# WorkingVersion_Final_Bread_Proofing_Box_.net
KiCad netlist of a schematic drawn in EAGLE
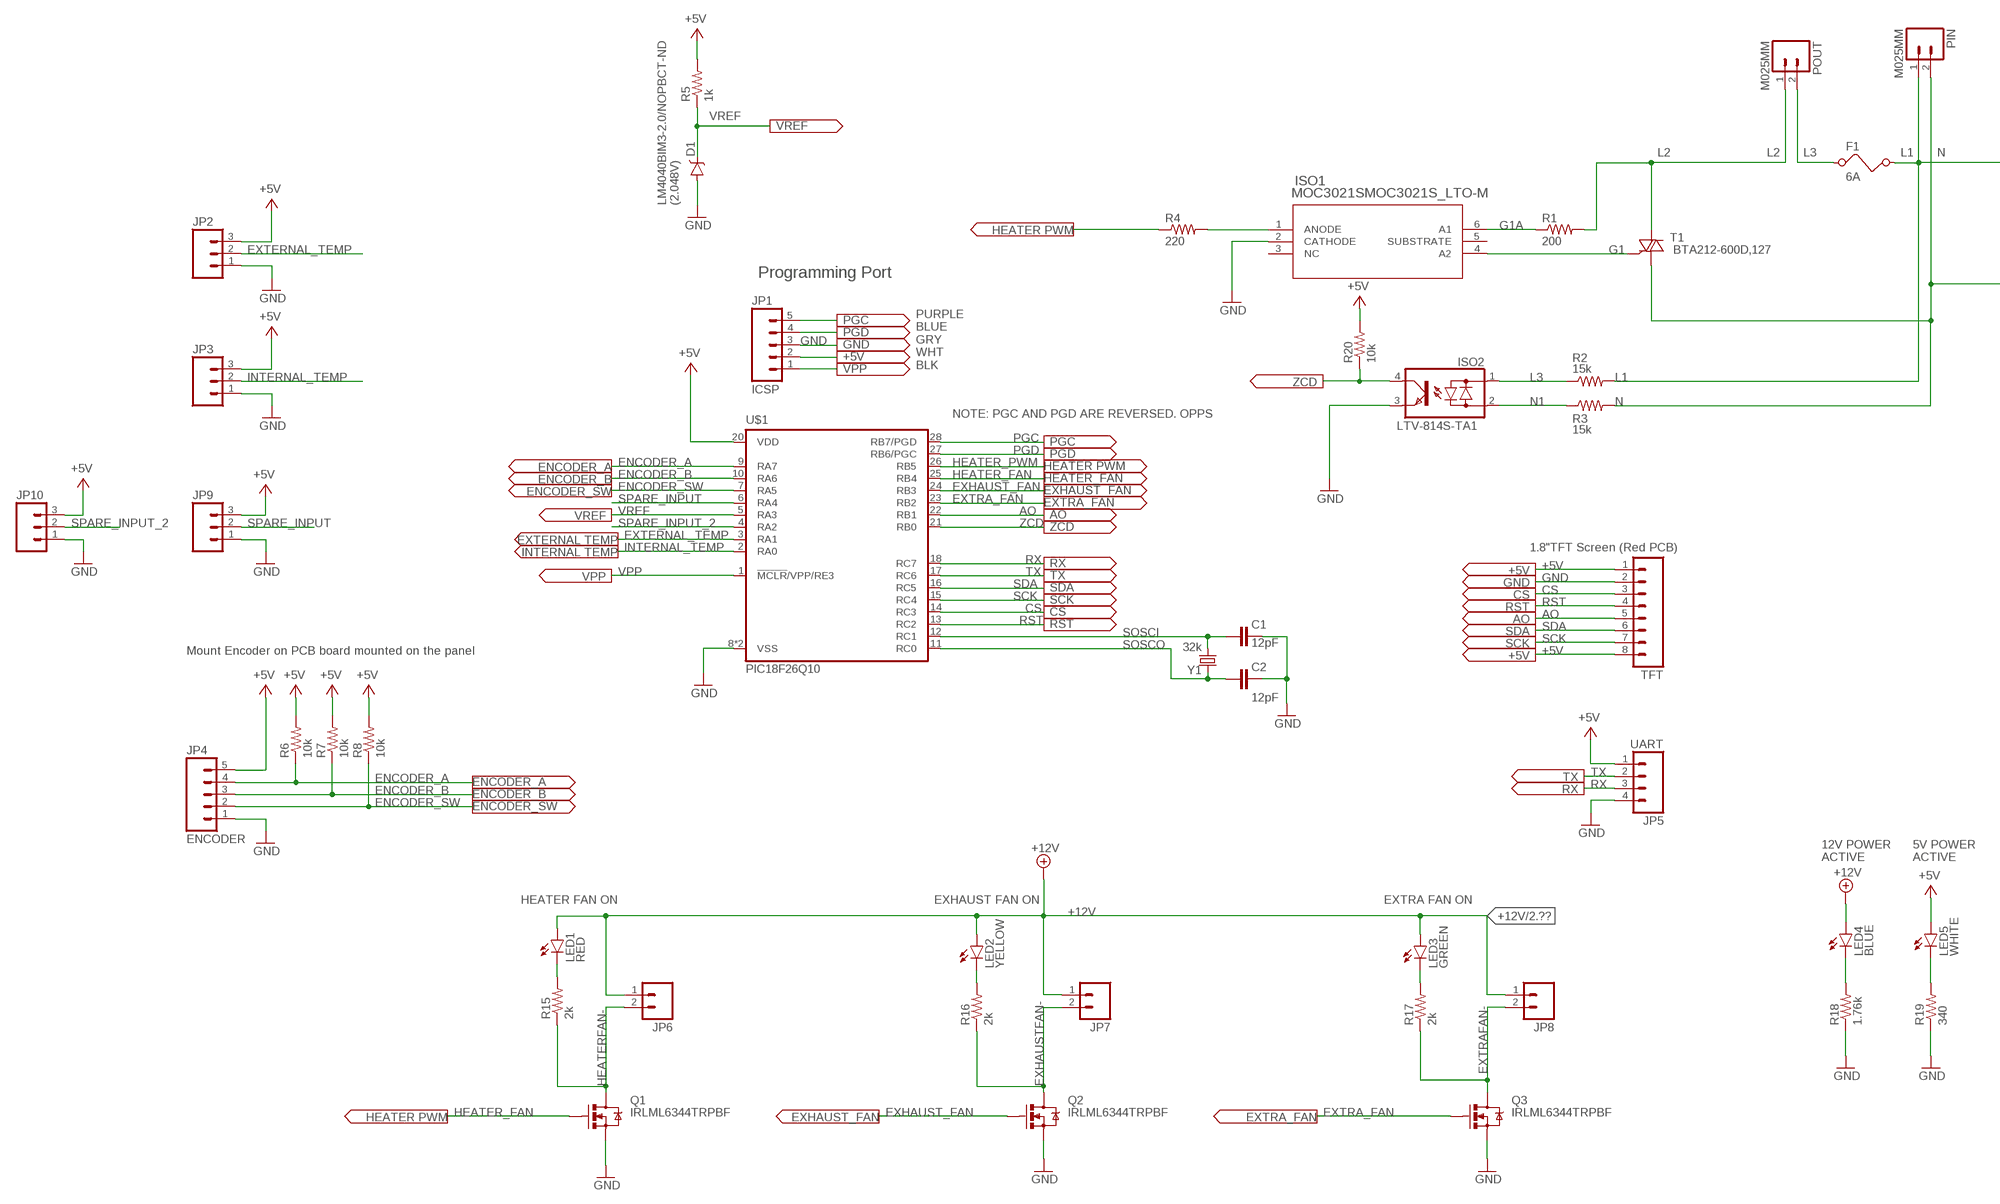
[diagram p0: schematic, sheet 1, part 1 of 2]
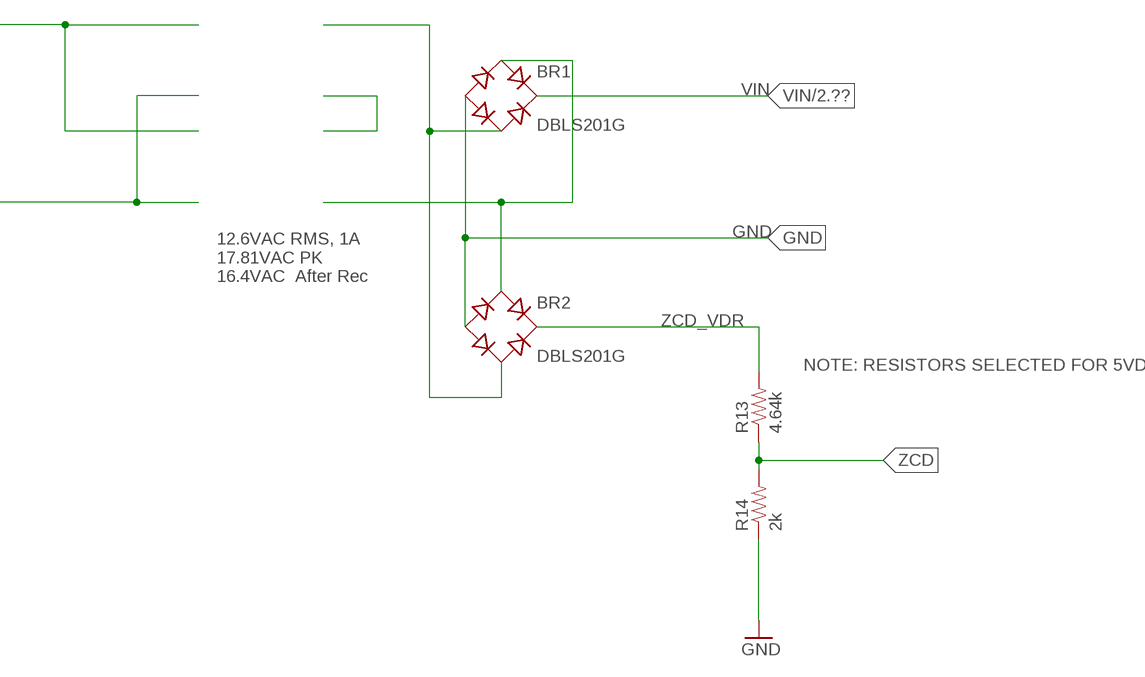
[diagram p1: schematic, sheet 1, part 2 of 2]
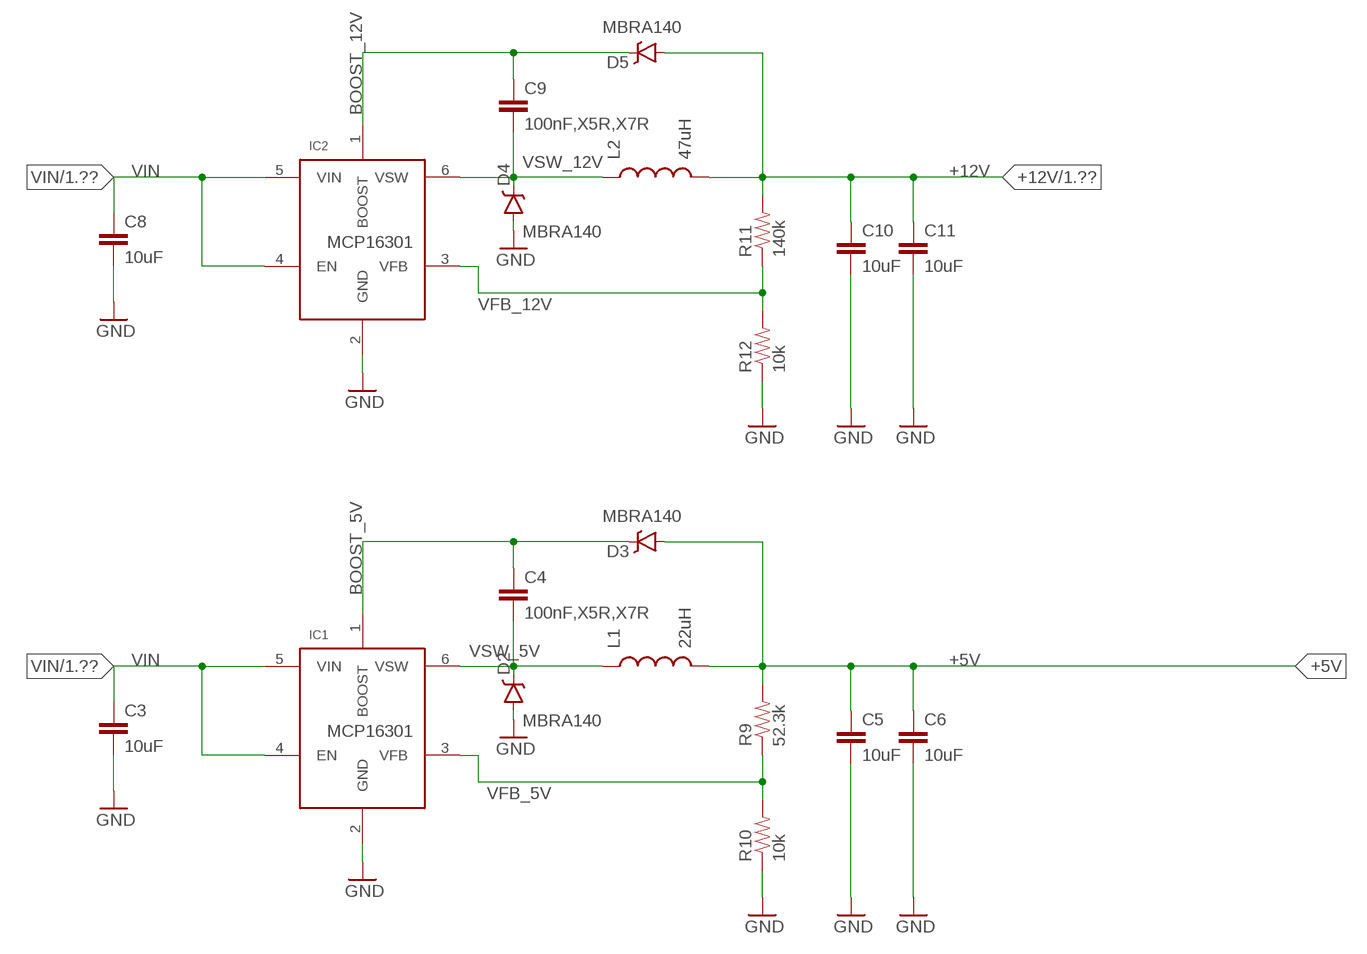
[diagram p2: schematic, sheet 2]

(export (version "E")
  (design (tool "Eeschema 10.0.6"))
  (components
    (comp (ref "C3")
      (value "10uF")
      (footprint "eagle-import:1206")
      (libsource (lib "eagle-import") (part "CAP1206"))
    )
    (comp (ref "C4")
      (value "100nF,X5R,X7R")
      (footprint "eagle-import:1206")
      (libsource (lib "eagle-import") (part "CAP1206"))
    )
    (comp (ref "C5")
      (value "10uF")
      (footprint "eagle-import:1206")
      (libsource (lib "eagle-import") (part "CAP1206"))
    )
    (comp (ref "C6")
      (value "10uF")
      (footprint "eagle-import:1206")
      (libsource (lib "eagle-import") (part "CAP1206"))
    )
    (comp (ref "C8")
      (value "10uF")
      (footprint "eagle-import:1206")
      (libsource (lib "eagle-import") (part "CAP1206"))
    )
    (comp (ref "C9")
      (value "100nF,X5R,X7R")
      (footprint "eagle-import:1206")
      (libsource (lib "eagle-import") (part "CAP1206"))
    )
    (comp (ref "C10")
      (value "10uF")
      (footprint "eagle-import:1206")
      (libsource (lib "eagle-import") (part "CAP1206"))
    )
    (comp (ref "C11")
      (value "10uF")
      (footprint "eagle-import:1206")
      (libsource (lib "eagle-import") (part "CAP1206"))
    )
    (comp (ref "D2")
      (value "MBRA140")
      (footprint "eagle-import:SMA-DIODE")
      (libsource (lib "eagle-import") (part "DIODE-SCHOTTKY-MBRA140"))
    )
    (comp (ref "D3")
      (value "MBRA140")
      (footprint "eagle-import:SMA-DIODE")
      (libsource (lib "eagle-import") (part "DIODE-SCHOTTKY-MBRA140"))
    )
    (comp (ref "D4")
      (value "MBRA140")
      (footprint "eagle-import:SMA-DIODE")
      (libsource (lib "eagle-import") (part "DIODE-SCHOTTKY-MBRA140"))
    )
    (comp (ref "D5")
      (value "MBRA140")
      (footprint "eagle-import:SMA-DIODE")
      (libsource (lib "eagle-import") (part "DIODE-SCHOTTKY-MBRA140"))
    )
    (comp (ref "IC1")
      (value "MCP16301")
      (footprint "eagle-import:SOT23-6")
      (libsource (lib "eagle-import") (part "MCP16301"))
    )
    (comp (ref "IC2")
      (value "MCP16301")
      (footprint "eagle-import:SOT23-6")
      (libsource (lib "eagle-import") (part "MCP16301"))
    )
    (comp (ref "L1")
      (value "22uH")
      (footprint "eagle-import:1210")
      (libsource (lib "eagle-import") (part "INDUCTOR1210"))
    )
    (comp (ref "L2")
      (value "47uH")
      (footprint "eagle-import:1210")
      (libsource (lib "eagle-import") (part "INDUCTOR1210"))
    )
    (comp (ref "R9")
      (value "52.3k")
      (footprint "eagle-import:1206")
      (libsource (lib "eagle-import") (part "RESISTOR1206"))
    )
    (comp (ref "R10")
      (value "10k")
      (footprint "eagle-import:1206")
      (libsource (lib "eagle-import") (part "RESISTOR1206"))
    )
    (comp (ref "R11")
      (value "140k")
      (footprint "eagle-import:1206")
      (libsource (lib "eagle-import") (part "RESISTOR1206"))
    )
    (comp (ref "R12")
      (value "10k")
      (footprint "eagle-import:1206")
      (libsource (lib "eagle-import") (part "RESISTOR1206"))
    )
    (comp (ref "BR1")
      (value "DBLS201G")
      (footprint "eagle-import:DBS")
      (libsource (lib "eagle-import") (part "DB?GLS201"))
    )
    (comp (ref "BR2")
      (value "DBLS201G")
      (footprint "eagle-import:DBS")
      (libsource (lib "eagle-import") (part "DB?GLS201"))
    )
    (comp (ref "C1")
      (value "12pF")
      (footprint "eagle-import:0805")
      (libsource (lib "eagle-import") (part "CAP0805"))
    )
    (comp (ref "C2")
      (value "12pF")
      (footprint "eagle-import:0805")
      (libsource (lib "eagle-import") (part "CAP0805"))
    )
    (comp (ref "D1")
      (value "V-REFERENCESMD")
      (footprint "eagle-import:SOT23-3")
      (libsource (lib "eagle-import") (part "V-REFERENCESMD"))
    )
    (comp (ref "F1")
      (value "6A")
      (footprint "eagle-import:FUSE")
      (libsource (lib "eagle-import") (part "FUSE"))
    )
    (comp (ref "ISO1")
      (value "MOC3021SMOC3021S_LTO-M")
      (footprint "eagle-import:MOC3021S_LTO-M")
      (fields
        (field (name "MANUFACTURER_PART_NUMBER") "MOC3021S")
        (field (name "COPYRIGHT") "Copyright (C) 2018 Accelerated Designs. All rights reserved")
      )
      (libsource (lib "eagle-import") (part "MOC3021SMOC3021S_LTO-M"))
    )
    (comp (ref "ISO2")
      (value "LTV-814S-TA1")
      (footprint "eagle-import:DIL4-SMD")
      (fields (field (name "MF") "VISHAY/TELEFUNKEN") (field (name "MPN") "SFH6206-3"))
      (libsource (lib "eagle-import") (part "SFH6206"))
    )
    (comp (ref "JP1")
      (value "ICSP")
      (footprint "eagle-import:1X05")
      (libsource (lib "eagle-import") (part "M05PTH"))
    )
    (comp (ref "JP2")
      (value "M03POLAR")
      (footprint "eagle-import:MOLEX-1X3")
      (libsource (lib "eagle-import") (part "M03POLAR"))
    )
    (comp (ref "JP3")
      (value "M03POLAR")
      (footprint "eagle-import:MOLEX-1X3")
      (libsource (lib "eagle-import") (part "M03POLAR"))
    )
    (comp (ref "JP4")
      (value "ENCODER")
      (footprint "eagle-import:1X05")
      (libsource (lib "eagle-import") (part "M05PTH"))
    )
    (comp (ref "JP5")
      (value "UART")
      (footprint "eagle-import:1X04_LOCK")
      (libsource (lib "eagle-import") (part "M04LOCK"))
    )
    (comp (ref "JP6")
      (value "M02POLAR_LOCK")
      (footprint "eagle-import:MOLEX-1X2_LOCK")
      (libsource (lib "eagle-import") (part "M02POLAR_LOCK"))
    )
    (comp (ref "JP7")
      (value "M02POLAR_LOCK")
      (footprint "eagle-import:MOLEX-1X2_LOCK")
      (libsource (lib "eagle-import") (part "M02POLAR_LOCK"))
    )
    (comp (ref "JP8")
      (value "M02POLAR_LOCK")
      (footprint "eagle-import:MOLEX-1X2_LOCK")
      (libsource (lib "eagle-import") (part "M02POLAR_LOCK"))
    )
    (comp (ref "JP9")
      (value "M03POLAR")
      (footprint "eagle-import:MOLEX-1X3")
      (libsource (lib "eagle-import") (part "M03POLAR"))
    )
    (comp (ref "JP10")
      (value "M03POLAR")
      (footprint "eagle-import:MOLEX-1X3")
      (libsource (lib "eagle-import") (part "M03POLAR"))
    )
    (comp (ref "LED1")
      (value "RED")
      (footprint "eagle-import:LED-1206")
      (libsource (lib "eagle-import") (part "LED1206"))
    )
    (comp (ref "LED2")
      (value "YELLOW")
      (footprint "eagle-import:LED-1206")
      (libsource (lib "eagle-import") (part "LED1206"))
    )
    (comp (ref "LED3")
      (value "GREEN")
      (footprint "eagle-import:LED-1206")
      (libsource (lib "eagle-import") (part "LED1206"))
    )
    (comp (ref "LED4")
      (value "BLUE")
      (footprint "eagle-import:LED-1206")
      (libsource (lib "eagle-import") (part "LED1206"))
    )
    (comp (ref "LED5")
      (value "WHITE")
      (footprint "eagle-import:LED-1206")
      (libsource (lib "eagle-import") (part "LED1206"))
    )
    (comp (ref "PIN")
      (value "M025MM")
      (footprint "eagle-import:SCREWTERMINAL-5MM-2")
      (libsource (lib "eagle-import") (part "M025MM"))
    )
    (comp (ref "POUT")
      (value "M025MM")
      (footprint "eagle-import:SCREWTERMINAL-5MM-2")
      (libsource (lib "eagle-import") (part "M025MM"))
    )
    (comp (ref "Q1")
      (value "IRLML6344TRPBF")
      (footprint "eagle-import:SOT323")
      (libsource (lib "eagle-import") (part "MOSFET-NCHANNEL2N7002PW"))
    )
    (comp (ref "Q2")
      (value "IRLML6344TRPBF")
      (footprint "eagle-import:SOT323")
      (libsource (lib "eagle-import") (part "MOSFET-NCHANNEL2N7002PW"))
    )
    (comp (ref "Q3")
      (value "IRLML6344TRPBF")
      (footprint "eagle-import:SOT323")
      (libsource (lib "eagle-import") (part "MOSFET-NCHANNEL2N7002PW"))
    )
    (comp (ref "R1")
      (value "200")
      (footprint "eagle-import:R2512")
      (libsource (lib "eagle-import") (part "R-US_R2512"))
    )
    (comp (ref "R2")
      (value "15k")
      (footprint "eagle-import:R2512")
      (libsource (lib "eagle-import") (part "R-US_R2512"))
    )
    (comp (ref "R3")
      (value "15k")
      (footprint "eagle-import:R2512")
      (libsource (lib "eagle-import") (part "R-US_R2512"))
    )
    (comp (ref "R4")
      (value "220")
      (footprint "eagle-import:1206")
      (libsource (lib "eagle-import") (part "RESISTOR1206"))
    )
    (comp (ref "R5")
      (value "1k")
      (footprint "eagle-import:1206")
      (libsource (lib "eagle-import") (part "RESISTOR1206"))
    )
    (comp (ref "R6")
      (value "10k")
      (footprint "eagle-import:1206")
      (libsource (lib "eagle-import") (part "RESISTOR1206"))
    )
    (comp (ref "R7")
      (value "10k")
      (footprint "eagle-import:1206")
      (libsource (lib "eagle-import") (part "RESISTOR1206"))
    )
    (comp (ref "R8")
      (value "10k")
      (footprint "eagle-import:1206")
      (libsource (lib "eagle-import") (part "RESISTOR1206"))
    )
    (comp (ref "R13")
      (value "4.64k")
      (footprint "eagle-import:1206")
      (libsource (lib "eagle-import") (part "RESISTOR1206"))
    )
    (comp (ref "R14")
      (value "2k")
      (footprint "eagle-import:1206")
      (libsource (lib "eagle-import") (part "RESISTOR1206"))
    )
    (comp (ref "R15")
      (value "2k")
      (footprint "eagle-import:1206")
      (libsource (lib "eagle-import") (part "RESISTOR1206"))
    )
    (comp (ref "R16")
      (value "2k")
      (footprint "eagle-import:1206")
      (libsource (lib "eagle-import") (part "RESISTOR1206"))
    )
    (comp (ref "R17")
      (value "2k")
      (footprint "eagle-import:1206")
      (libsource (lib "eagle-import") (part "RESISTOR1206"))
    )
    (comp (ref "R18")
      (value "1.76k")
      (footprint "eagle-import:1206")
      (libsource (lib "eagle-import") (part "RESISTOR1206"))
    )
    (comp (ref "R19")
      (value "340")
      (footprint "eagle-import:1206")
      (libsource (lib "eagle-import") (part "RESISTOR1206"))
    )
    (comp (ref "R20")
      (value "10k")
      (footprint "eagle-import:1206")
      (libsource (lib "eagle-import") (part "RESISTOR1206"))
    )
    (comp (ref "T1")
      (value "BTA212-600D,127")
      (footprint "eagle-import:TO220BV")
      (libsource (lib "eagle-import") (part "BT138-V"))
    )
    (comp (ref "TFT")
      (value "M08LOCK")
      (footprint "eagle-import:1X08_LOCK")
      (libsource (lib "eagle-import") (part "M08LOCK"))
    )
    (comp (ref "U$1")
      (value "PIC18F26Q10")
      (footprint "eagle-import:SO28W")
      (libsource (lib "eagle-import") (part "PIC18F25K22SOIC"))
    )
    (comp (ref "Y1")
      (value "32k")
      (footprint "eagle-import:TC26V")
      (libsource (lib "eagle-import") (part "CRYSTALTC26V"))
    )
  )
  (nets
    (net (code "1") (name "+5V") (class "Default")
      (node (ref "C5") (pin "1") (pinfunction "1_1") (pintype "passive"))
      (node (ref "C6") (pin "1") (pinfunction "1_1") (pintype "passive"))
      (node (ref "D3") (pin "A") (pinfunction "A_A") (pintype "passive"))
      (node (ref "JP1") (pin "2") (pinfunction "2_2") (pintype "passive"))
      (node (ref "JP10") (pin "3") (pinfunction "3_3") (pintype "passive"))
      (node (ref "JP2") (pin "3") (pinfunction "3_3") (pintype "passive"))
      (node (ref "JP3") (pin "3") (pinfunction "3_3") (pintype "passive"))
      (node (ref "JP4") (pin "5") (pinfunction "5_5") (pintype "passive"))
      (node (ref "JP5") (pin "1") (pinfunction "1_1") (pintype "passive"))
      (node (ref "JP9") (pin "3") (pinfunction "3_3") (pintype "passive"))
      (node (ref "L1") (pin "2") (pinfunction "2_2") (pintype "passive"))
      (node (ref "LED5") (pin "A") (pinfunction "A_A") (pintype "passive"))
      (node (ref "R20") (pin "2") (pinfunction "2_2") (pintype "passive"))
      (node (ref "R5") (pin "2") (pinfunction "2_2") (pintype "passive"))
      (node (ref "R6") (pin "2") (pinfunction "2_2") (pintype "passive"))
      (node (ref "R7") (pin "2") (pinfunction "2_2") (pintype "passive"))
      (node (ref "R8") (pin "2") (pinfunction "2_2") (pintype "passive"))
      (node (ref "R9") (pin "2") (pinfunction "2_2") (pintype "passive"))
      (node (ref "TFT") (pin "1") (pinfunction "1_1") (pintype "passive"))
      (node (ref "TFT") (pin "8") (pinfunction "8_8") (pintype "passive"))
      (node (ref "U$1") (pin "20") (pinfunction "VDD_20") (pintype "power_in"))
    )
    (net (code "2") (name "+12V") (class "Default")
      (node (ref "C10") (pin "1") (pinfunction "1_1") (pintype "passive"))
      (node (ref "C11") (pin "1") (pinfunction "1_1") (pintype "passive"))
      (node (ref "D5") (pin "A") (pinfunction "A_A") (pintype "passive"))
      (node (ref "JP6") (pin "1") (pinfunction "1_1") (pintype "passive"))
      (node (ref "JP7") (pin "1") (pinfunction "1_1") (pintype "passive"))
      (node (ref "JP8") (pin "1") (pinfunction "1_1") (pintype "passive"))
      (node (ref "L2") (pin "2") (pinfunction "2_2") (pintype "passive"))
      (node (ref "LED1") (pin "A") (pinfunction "A_A") (pintype "passive"))
      (node (ref "LED2") (pin "A") (pinfunction "A_A") (pintype "passive"))
      (node (ref "LED3") (pin "A") (pinfunction "A_A") (pintype "passive"))
      (node (ref "LED4") (pin "A") (pinfunction "A_A") (pintype "passive"))
      (node (ref "R11") (pin "2") (pinfunction "2_2") (pintype "passive"))
    )
    (net (code "3") (name "AO") (class "Default")
      (node (ref "TFT") (pin "5") (pinfunction "5_5") (pintype "passive"))
      (node (ref "U$1") (pin "22") (pinfunction "RB1_22") (pintype "bidirectional"))
    )
    (net (code "4") (name "BOOST_5V") (class "Default")
      (node (ref "C4") (pin "1") (pinfunction "1_1") (pintype "passive"))
      (node (ref "D3") (pin "C") (pinfunction "C_C") (pintype "passive"))
      (node (ref "IC1") (pin "1") (pinfunction "BOOST_1") (pintype "bidirectional"))
    )
    (net (code "5") (name "BOOST_12V") (class "Default")
      (node (ref "C9") (pin "1") (pinfunction "1_1") (pintype "passive"))
      (node (ref "D5") (pin "C") (pinfunction "C_C") (pintype "passive"))
      (node (ref "IC2") (pin "1") (pinfunction "BOOST_1") (pintype "bidirectional"))
    )
    (net (code "6") (name "CS") (class "Default")
      (node (ref "TFT") (pin "3") (pinfunction "3_3") (pintype "passive"))
      (node (ref "U$1") (pin "14") (pinfunction "RC3_14") (pintype "bidirectional"))
    )
    (net (code "7") (name "ENCODER_A") (class "Default")
      (node (ref "JP4") (pin "4") (pinfunction "4_4") (pintype "passive"))
      (node (ref "R6") (pin "1") (pinfunction "1_1") (pintype "passive"))
      (node (ref "U$1") (pin "9") (pinfunction "RA7_9") (pintype "bidirectional"))
    )
    (net (code "8") (name "ENCODER_B") (class "Default")
      (node (ref "JP4") (pin "3") (pinfunction "3_3") (pintype "passive"))
      (node (ref "R7") (pin "1") (pinfunction "1_1") (pintype "passive"))
      (node (ref "U$1") (pin "10") (pinfunction "RA6_10") (pintype "bidirectional"))
    )
    (net (code "9") (name "ENCODER_SW") (class "Default")
      (node (ref "JP4") (pin "2") (pinfunction "2_2") (pintype "passive"))
      (node (ref "R8") (pin "1") (pinfunction "1_1") (pintype "passive"))
      (node (ref "U$1") (pin "7") (pinfunction "RA5_7") (pintype "bidirectional"))
    )
    (net (code "10") (name "EXHAUSTFAN-") (class "Default")
      (node (ref "JP7") (pin "2") (pinfunction "2_2") (pintype "passive"))
      (node (ref "Q2") (pin "3") (pinfunction "D_3") (pintype "passive"))
      (node (ref "R16") (pin "1") (pinfunction "1_1") (pintype "passive"))
    )
    (net (code "11") (name "EXHAUST_FAN") (class "Default")
      (node (ref "Q2") (pin "1") (pinfunction "G_1") (pintype "passive"))
      (node (ref "U$1") (pin "24") (pinfunction "RB3_24") (pintype "bidirectional"))
    )
    (net (code "12") (name "EXTERNAL_TEMP") (class "Default")
      (node (ref "JP2") (pin "2") (pinfunction "2_2") (pintype "passive"))
      (node (ref "U$1") (pin "3") (pinfunction "RA1_3") (pintype "bidirectional"))
    )
    (net (code "13") (name "EXTRAFAN-") (class "Default")
      (node (ref "JP8") (pin "2") (pinfunction "2_2") (pintype "passive"))
      (node (ref "Q3") (pin "3") (pinfunction "D_3") (pintype "passive"))
      (node (ref "R17") (pin "1") (pinfunction "1_1") (pintype "passive"))
    )
    (net (code "14") (name "EXTRA_FAN") (class "Default")
      (node (ref "Q3") (pin "1") (pinfunction "G_1") (pintype "passive"))
      (node (ref "U$1") (pin "23") (pinfunction "RB2_23") (pintype "bidirectional"))
    )
    (net (code "15") (name "G1") (class "Default")
      (node (ref "ISO1") (pin "4") (pinfunction "A2_4") (pintype "passive"))
      (node (ref "T1") (pin "G") (pinfunction "G_G") (pintype "passive"))
    )
    (net (code "16") (name "G1A") (class "Default")
      (node (ref "ISO1") (pin "6") (pinfunction "A1_6") (pintype "passive"))
      (node (ref "R1") (pin "1") (pinfunction "1_1") (pintype "passive"))
    )
    (net (code "17") (name "GND") (class "Default")
      (node (ref "BR1") (pin "-") (pinfunction "-_-") (pintype "passive"))
      (node (ref "BR2") (pin "-") (pinfunction "-_-") (pintype "passive"))
      (node (ref "C1") (pin "2") (pinfunction "2_2") (pintype "passive"))
      (node (ref "C10") (pin "2") (pinfunction "2_2") (pintype "passive"))
      (node (ref "C11") (pin "2") (pinfunction "2_2") (pintype "passive"))
      (node (ref "C2") (pin "2") (pinfunction "2_2") (pintype "passive"))
      (node (ref "C3") (pin "2") (pinfunction "2_2") (pintype "passive"))
      (node (ref "C5") (pin "2") (pinfunction "2_2") (pintype "passive"))
      (node (ref "C6") (pin "2") (pinfunction "2_2") (pintype "passive"))
      (node (ref "C8") (pin "2") (pinfunction "2_2") (pintype "passive"))
      (node (ref "D1") (pin "2") (pinfunction "A_2") (pintype "passive"))
      (node (ref "D2") (pin "A") (pinfunction "A_A") (pintype "passive"))
      (node (ref "D4") (pin "A") (pinfunction "A_A") (pintype "passive"))
      (node (ref "IC1") (pin "2") (pinfunction "GND_2") (pintype "bidirectional"))
      (node (ref "IC2") (pin "2") (pinfunction "GND_2") (pintype "bidirectional"))
      (node (ref "ISO1") (pin "2") (pinfunction "CATHODE_2") (pintype "passive"))
      (node (ref "ISO2") (pin "3") (pinfunction "E_3") (pintype "passive"))
      (node (ref "JP1") (pin "3") (pinfunction "3_3") (pintype "passive"))
      (node (ref "JP10") (pin "1") (pinfunction "1_1") (pintype "passive"))
      (node (ref "JP2") (pin "1") (pinfunction "1_1") (pintype "passive"))
      (node (ref "JP3") (pin "1") (pinfunction "1_1") (pintype "passive"))
      (node (ref "JP4") (pin "1") (pinfunction "1_1") (pintype "passive"))
      (node (ref "JP5") (pin "4") (pinfunction "4_4") (pintype "passive"))
      (node (ref "JP9") (pin "1") (pinfunction "1_1") (pintype "passive"))
      (node (ref "Q1") (pin "2") (pinfunction "S_2") (pintype "passive"))
      (node (ref "Q2") (pin "2") (pinfunction "S_2") (pintype "passive"))
      (node (ref "Q3") (pin "2") (pinfunction "S_2") (pintype "passive"))
      (node (ref "R10") (pin "1") (pinfunction "1_1") (pintype "passive"))
      (node (ref "R12") (pin "1") (pinfunction "1_1") (pintype "passive"))
      (node (ref "R14") (pin "1") (pinfunction "1_1") (pintype "passive"))
      (node (ref "R18") (pin "1") (pinfunction "1_1") (pintype "passive"))
      (node (ref "R19") (pin "1") (pinfunction "1_1") (pintype "passive"))
      (node (ref "TFT") (pin "2") (pinfunction "2_2") (pintype "passive"))
      (node (ref "U$1") (pin "19") (pinfunction "VSS_19") (pintype "power_in"))
      (node (ref "U$1") (pin "8") (pinfunction "VSS_8") (pintype "power_in"))
    )
    (net (code "18") (name "HEATERFAN-") (class "Default")
      (node (ref "JP6") (pin "2") (pinfunction "2_2") (pintype "passive"))
      (node (ref "Q1") (pin "3") (pinfunction "D_3") (pintype "passive"))
      (node (ref "R15") (pin "1") (pinfunction "1_1") (pintype "passive"))
    )
    (net (code "19") (name "HEATER_FAN") (class "Default")
      (node (ref "Q1") (pin "1") (pinfunction "G_1") (pintype "passive"))
      (node (ref "U$1") (pin "25") (pinfunction "RB4_25") (pintype "bidirectional"))
    )
    (net (code "20") (name "HEATER_PWM") (class "Default")
      (node (ref "R4") (pin "1") (pinfunction "1_1") (pintype "passive"))
      (node (ref "U$1") (pin "26") (pinfunction "RB5_26") (pintype "bidirectional"))
    )
    (net (code "21") (name "INTERNAL_TEMP") (class "Default")
      (node (ref "JP3") (pin "2") (pinfunction "2_2") (pintype "passive"))
      (node (ref "U$1") (pin "2") (pinfunction "RA0_2") (pintype "bidirectional"))
    )
    (net (code "22") (name "L1") (class "Default")
      (node (ref "F1") (pin "2") (pinfunction "2_2") (pintype "passive"))
      (node (ref "PIN") (pin "1") (pinfunction "1_1") (pintype "passive"))
      (node (ref "R2") (pin "2") (pinfunction "2_2") (pintype "passive"))
    )
    (net (code "23") (name "L2") (class "Default")
      (node (ref "POUT") (pin "1") (pinfunction "1_1") (pintype "passive"))
      (node (ref "R1") (pin "2") (pinfunction "2_2") (pintype "passive"))
      (node (ref "T1") (pin "T2") (pinfunction "A2_T2") (pintype "passive"))
    )
    (net (code "24") (name "L3") (class "Default")
      (node (ref "F1") (pin "1") (pinfunction "1_1") (pintype "passive"))
      (node (ref "ISO2") (pin "1") (pinfunction "AC1_1") (pintype "passive"))
      (node (ref "POUT") (pin "2") (pinfunction "2_2") (pintype "passive"))
      (node (ref "R2") (pin "1") (pinfunction "1_1") (pintype "passive"))
    )
    (net (code "25") (name "N") (class "Default")
      (node (ref "PIN") (pin "2") (pinfunction "2_2") (pintype "passive"))
      (node (ref "R3") (pin "2") (pinfunction "2_2") (pintype "passive"))
      (node (ref "T1") (pin "T1") (pinfunction "A1_T1") (pintype "passive"))
    )
    (net (code "26") (name "N1") (class "Default")
      (node (ref "ISO2") (pin "2") (pinfunction "AC2_2") (pintype "passive"))
      (node (ref "R3") (pin "1") (pinfunction "1_1") (pintype "passive"))
    )
    (net (code "27") (name "Net-(BR1-PadAC1)") (class "Default")
      (node (ref "BR1") (pin "AC1") (pinfunction "AC1_AC1") (pintype "passive"))
      (node (ref "BR2") (pin "AC1") (pinfunction "AC1_AC1") (pintype "passive"))
    )
    (net (code "28") (name "Net-(BR1-PadAC2)") (class "Default")
      (node (ref "BR1") (pin "AC2") (pinfunction "AC2_AC2") (pintype "passive"))
      (node (ref "BR2") (pin "AC2") (pinfunction "AC2_AC2") (pintype "passive"))
    )
    (net (code "29") (name "Net-(ISO1-ANODE)") (class "Default")
      (node (ref "ISO1") (pin "1") (pinfunction "ANODE_1") (pintype "passive"))
      (node (ref "R4") (pin "2") (pinfunction "2_2") (pintype "passive"))
    )
    (net (code "30") (name "Net-(LED1-PadC)") (class "Default")
      (node (ref "LED1") (pin "C") (pinfunction "C_C") (pintype "passive"))
      (node (ref "R15") (pin "2") (pinfunction "2_2") (pintype "passive"))
    )
    (net (code "31") (name "Net-(LED2-PadC)") (class "Default")
      (node (ref "LED2") (pin "C") (pinfunction "C_C") (pintype "passive"))
      (node (ref "R16") (pin "2") (pinfunction "2_2") (pintype "passive"))
    )
    (net (code "32") (name "Net-(LED3-PadC)") (class "Default")
      (node (ref "LED3") (pin "C") (pinfunction "C_C") (pintype "passive"))
      (node (ref "R17") (pin "2") (pinfunction "2_2") (pintype "passive"))
    )
    (net (code "33") (name "Net-(LED4-PadC)") (class "Default")
      (node (ref "LED4") (pin "C") (pinfunction "C_C") (pintype "passive"))
      (node (ref "R18") (pin "2") (pinfunction "2_2") (pintype "passive"))
    )
    (net (code "34") (name "Net-(LED5-PadC)") (class "Default")
      (node (ref "LED5") (pin "C") (pinfunction "C_C") (pintype "passive"))
      (node (ref "R19") (pin "2") (pinfunction "2_2") (pintype "passive"))
    )
    (net (code "35") (name "PGC") (class "Default")
      (node (ref "JP1") (pin "5") (pinfunction "5_5") (pintype "passive"))
      (node (ref "U$1") (pin "28") (pinfunction "RB7/PGD_28") (pintype "bidirectional"))
    )
    (net (code "36") (name "PGD") (class "Default")
      (node (ref "JP1") (pin "4") (pinfunction "4_4") (pintype "passive"))
      (node (ref "U$1") (pin "27") (pinfunction "RB6/PGC_27") (pintype "bidirectional"))
    )
    (net (code "37") (name "RST") (class "Default")
      (node (ref "TFT") (pin "4") (pinfunction "4_4") (pintype "passive"))
      (node (ref "U$1") (pin "13") (pinfunction "RC2_13") (pintype "bidirectional"))
    )
    (net (code "38") (name "RX") (class "Default")
      (node (ref "JP5") (pin "3") (pinfunction "3_3") (pintype "passive"))
      (node (ref "U$1") (pin "18") (pinfunction "RC7_18") (pintype "bidirectional"))
    )
    (net (code "39") (name "SCK") (class "Default")
      (node (ref "TFT") (pin "7") (pinfunction "7_7") (pintype "passive"))
      (node (ref "U$1") (pin "15") (pinfunction "RC4_15") (pintype "bidirectional"))
    )
    (net (code "40") (name "SDA") (class "Default")
      (node (ref "TFT") (pin "6") (pinfunction "6_6") (pintype "passive"))
      (node (ref "U$1") (pin "16") (pinfunction "RC5_16") (pintype "bidirectional"))
    )
    (net (code "41") (name "SOSCI") (class "Default")
      (node (ref "C1") (pin "1") (pinfunction "1_1") (pintype "passive"))
      (node (ref "U$1") (pin "12") (pinfunction "RC1_12") (pintype "bidirectional"))
      (node (ref "Y1") (pin "1") (pinfunction "1_1") (pintype "passive"))
    )
    (net (code "42") (name "SOSCO") (class "Default")
      (node (ref "C2") (pin "1") (pinfunction "1_1") (pintype "passive"))
      (node (ref "U$1") (pin "11") (pinfunction "RC0_11") (pintype "bidirectional"))
      (node (ref "Y1") (pin "2") (pinfunction "2_2") (pintype "passive"))
    )
    (net (code "43") (name "SPARE_INPUT") (class "Default")
      (node (ref "JP9") (pin "2") (pinfunction "2_2") (pintype "passive"))
      (node (ref "U$1") (pin "6") (pinfunction "RA4_6") (pintype "bidirectional"))
    )
    (net (code "44") (name "SPARE_INPUT_2") (class "Default")
      (node (ref "JP10") (pin "2") (pinfunction "2_2") (pintype "passive"))
      (node (ref "U$1") (pin "4") (pinfunction "RA2_4") (pintype "bidirectional"))
    )
    (net (code "45") (name "TX") (class "Default")
      (node (ref "JP5") (pin "2") (pinfunction "2_2") (pintype "passive"))
      (node (ref "U$1") (pin "17") (pinfunction "RC6_17") (pintype "bidirectional"))
    )
    (net (code "46") (name "VFB_5V") (class "Default")
      (node (ref "IC1") (pin "3") (pinfunction "VFB_3") (pintype "bidirectional"))
      (node (ref "R10") (pin "2") (pinfunction "2_2") (pintype "passive"))
      (node (ref "R9") (pin "1") (pinfunction "1_1") (pintype "passive"))
    )
    (net (code "47") (name "VFB_12V") (class "Default")
      (node (ref "IC2") (pin "3") (pinfunction "VFB_3") (pintype "bidirectional"))
      (node (ref "R11") (pin "1") (pinfunction "1_1") (pintype "passive"))
      (node (ref "R12") (pin "2") (pinfunction "2_2") (pintype "passive"))
    )
    (net (code "48") (name "VIN") (class "Default")
      (node (ref "BR1") (pin "+") (pinfunction "+_+") (pintype "passive"))
      (node (ref "C3") (pin "1") (pinfunction "1_1") (pintype "passive"))
      (node (ref "C8") (pin "1") (pinfunction "1_1") (pintype "passive"))
      (node (ref "IC1") (pin "4") (pinfunction "EN_4") (pintype "bidirectional"))
      (node (ref "IC1") (pin "5") (pinfunction "VIN_5") (pintype "bidirectional"))
      (node (ref "IC2") (pin "4") (pinfunction "EN_4") (pintype "bidirectional"))
      (node (ref "IC2") (pin "5") (pinfunction "VIN_5") (pintype "bidirectional"))
    )
    (net (code "49") (name "VPP") (class "Default")
      (node (ref "JP1") (pin "1") (pinfunction "1_1") (pintype "passive"))
      (node (ref "U$1") (pin "1") (pinfunction "~{MCLR}/VPP/RE3_1") (pintype "bidirectional"))
    )
    (net (code "50") (name "VREF") (class "Default")
      (node (ref "D1") (pin "1") (pinfunction "C_1") (pintype "passive"))
      (node (ref "R5") (pin "1") (pinfunction "1_1") (pintype "passive"))
      (node (ref "U$1") (pin "5") (pinfunction "RA3_5") (pintype "bidirectional"))
    )
    (net (code "51") (name "VSW_5V") (class "Default")
      (node (ref "C4") (pin "2") (pinfunction "2_2") (pintype "passive"))
      (node (ref "D2") (pin "C") (pinfunction "C_C") (pintype "passive"))
      (node (ref "IC1") (pin "6") (pinfunction "VSW_6") (pintype "bidirectional"))
      (node (ref "L1") (pin "1") (pinfunction "1_1") (pintype "passive"))
    )
    (net (code "52") (name "VSW_12V") (class "Default")
      (node (ref "C9") (pin "2") (pinfunction "2_2") (pintype "passive"))
      (node (ref "D4") (pin "C") (pinfunction "C_C") (pintype "passive"))
      (node (ref "IC2") (pin "6") (pinfunction "VSW_6") (pintype "bidirectional"))
      (node (ref "L2") (pin "1") (pinfunction "1_1") (pintype "passive"))
    )
    (net (code "53") (name "ZCD") (class "Default")
      (node (ref "ISO2") (pin "4") (pinfunction "C_4") (pintype "passive"))
      (node (ref "R13") (pin "1") (pinfunction "1_1") (pintype "passive"))
      (node (ref "R14") (pin "2") (pinfunction "2_2") (pintype "passive"))
      (node (ref "R20") (pin "1") (pinfunction "1_1") (pintype "passive"))
      (node (ref "U$1") (pin "21") (pinfunction "RB0_21") (pintype "bidirectional"))
    )
    (net (code "54") (name "ZCD_VDR") (class "Default")
      (node (ref "BR2") (pin "+") (pinfunction "+_+") (pintype "passive"))
      (node (ref "R13") (pin "2") (pinfunction "2_2") (pintype "passive"))
    )
    (net (code "55") (name "unconnected-(ISO1-NC-Pad3)") (class "Default")
      (node (ref "ISO1") (pin "3") (pinfunction "NC_3") (pintype "passive"))
    )
    (net (code "56") (name "unconnected-(ISO1-SUBSTRATE-Pad5)") (class "Default")
      (node (ref "ISO1") (pin "5") (pinfunction "SUBSTRATE_5") (pintype "passive"))
    )
  )
)
